# 05-Power_Sources.net
KiCad netlist of a schematic drawn in Altium Designer
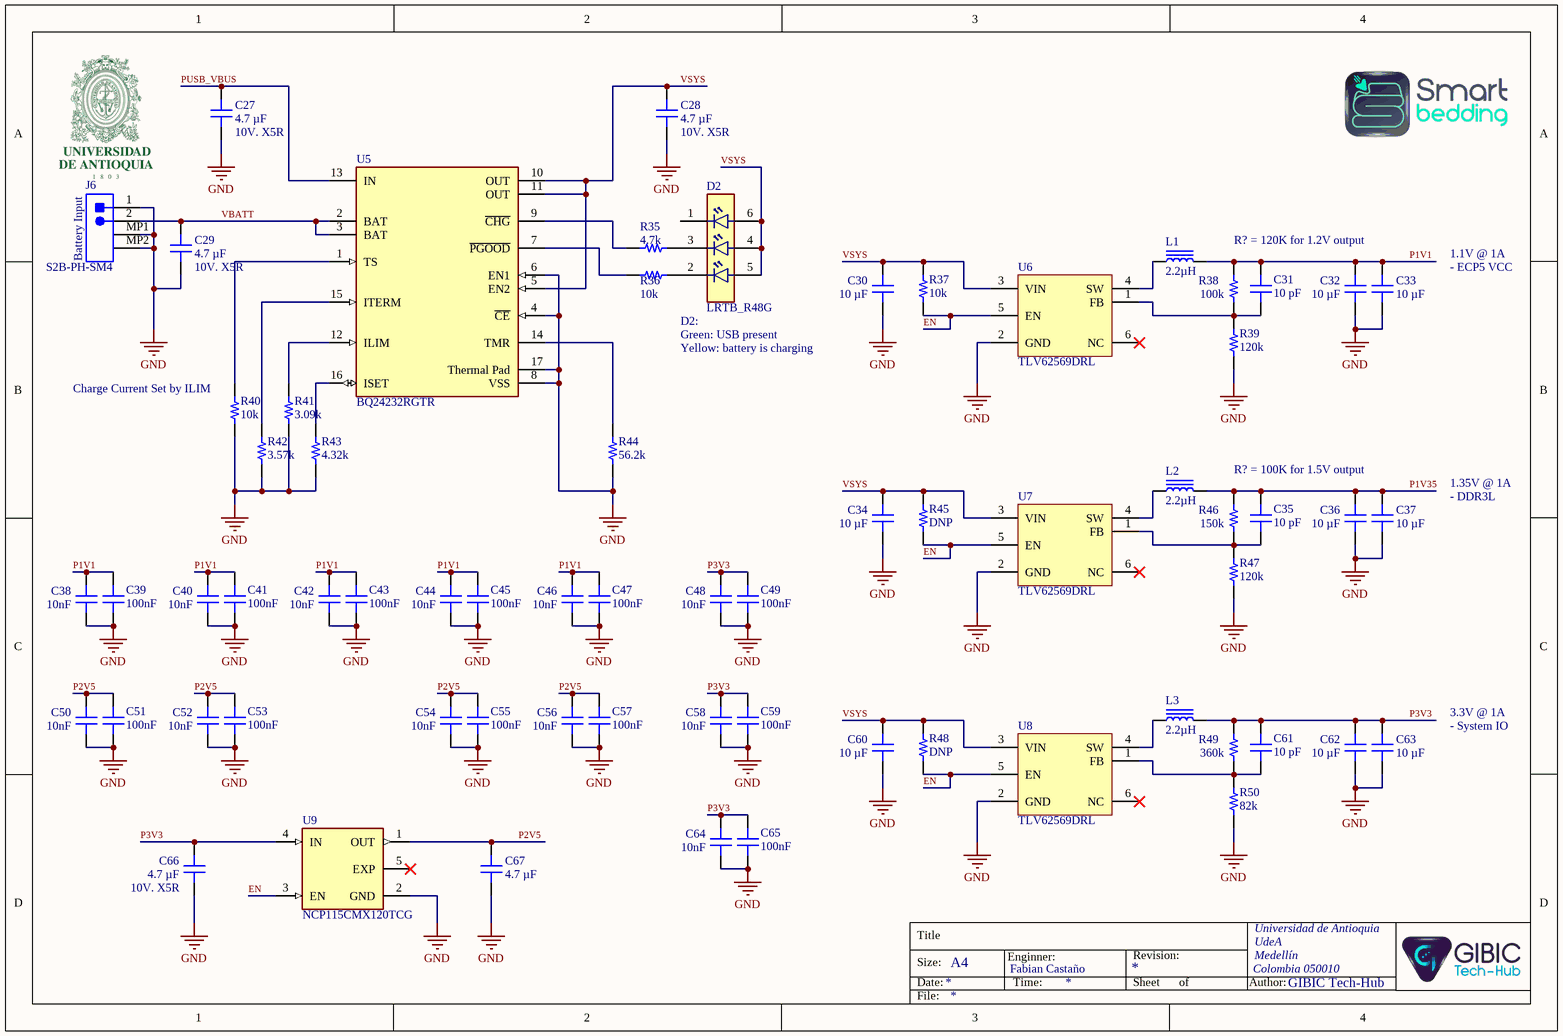
[diagram p0: 05-Power_Sources.SchDoc]

(export (version "E")
  (design (tool "Eeschema 10.0.6"))
  (components
    (comp (ref "C27")
      (value "4.7 µF")
      (footprint "CAP 0402_1005")
      (description "CAP CER 4.7UF 4V X6S 0402")
      (fields
        (field (name "PART NUMBER") "C1005X6S0G475M050BC")
        (field (name "MANUFACTURER") "TDK Corporation")
        (field (name "VOLTAGE") "10V. X5R")
        (field (name "LASTUPDATED") "3/01/2023 8:04:20 p. m.")
      )
      (libsource (lib "Celestial Altium Library - altium_library") (part "Capacitor"))
    )
    (comp (ref "C28")
      (value "4.7 µF")
      (footprint "CAP 0402_1005")
      (description "CAP CER 4.7UF 4V X6S 0402")
      (fields
        (field (name "PART NUMBER") "C1005X6S0G475M050BC")
        (field (name "MANUFACTURER") "TDK Corporation")
        (field (name "VOLTAGE") "10V. X5R")
        (field (name "LASTUPDATED") "3/01/2023 8:04:20 p. m.")
      )
      (libsource (lib "Celestial Altium Library - altium_library") (part "Capacitor"))
    )
    (comp (ref "C29")
      (value "4.7 µF")
      (footprint "CAP 0402_1005")
      (description "CAP CER 4.7UF 4V X6S 0402")
      (fields
        (field (name "PART NUMBER") "C1005X6S0G475M050BC")
        (field (name "MANUFACTURER") "TDK Corporation")
        (field (name "VOLTAGE") "10V. X5R")
        (field (name "LASTUPDATED") "3/01/2023 8:04:20 p. m.")
      )
      (libsource (lib "Celestial Altium Library - altium_library") (part "Capacitor"))
    )
    (comp (ref "C30")
      (value "10 µF")
      (footprint "CAP 0402_1005")
      (description "CAP CER 10UF 10V X5R 0402")
      (fields
        (field (name "PART NUMBER") "CL05A106MP8NUB8")
        (field (name "MANUFACTURER") "Samsung Electro-Mechanics")
        (field (name "LASTUPDATED") "3/01/2023 8:04:20 p. m.")
      )
      (libsource (lib "Celestial Altium Library - altium_library") (part "Capacitor"))
    )
    (comp (ref "C31")
      (value "10 pF")
      (footprint "CAP 0201_0603")
      (description "CAP CER 10PF 25V C0G/NP0 0201")
      (fields
        (field (name "PART NUMBER") "C0201C100J3GAC7867")
        (field (name "MANUFACTURER") "KEMET")
        (field (name "LASTUPDATED") "3/01/2023 8:01:19 p. m.")
      )
      (libsource (lib "Celestial Altium Library - altium_library") (part "Capacitor"))
    )
    (comp (ref "C32")
      (value "10 µF")
      (footprint "CAP 0402_1005")
      (description "CAP CER 10UF 10V X5R 0402")
      (fields
        (field (name "PART NUMBER") "CL05A106MP8NUB8")
        (field (name "MANUFACTURER") "Samsung Electro-Mechanics")
        (field (name "LASTUPDATED") "3/01/2023 8:04:20 p. m.")
      )
      (libsource (lib "Celestial Altium Library - altium_library") (part "Capacitor"))
    )
    (comp (ref "C33")
      (value "10 µF")
      (footprint "CAP 0402_1005")
      (description "CAP CER 10UF 10V X5R 0402")
      (fields
        (field (name "PART NUMBER") "CL05A106MP8NUB8")
        (field (name "MANUFACTURER") "Samsung Electro-Mechanics")
        (field (name "LASTUPDATED") "3/01/2023 8:04:20 p. m.")
      )
      (libsource (lib "Celestial Altium Library - altium_library") (part "Capacitor"))
    )
    (comp (ref "C34")
      (value "10 µF")
      (footprint "CAP 0402_1005")
      (description "CAP CER 10UF 10V X5R 0402")
      (fields
        (field (name "PART NUMBER") "CL05A106MP8NUB8")
        (field (name "MANUFACTURER") "Samsung Electro-Mechanics")
        (field (name "LASTUPDATED") "3/01/2023 8:04:20 p. m.")
      )
      (libsource (lib "Celestial Altium Library - altium_library") (part "Capacitor"))
    )
    (comp (ref "C35")
      (value "10 pF")
      (footprint "CAP 0201_0603")
      (description "CAP CER 10PF 25V C0G/NP0 0201")
      (fields
        (field (name "PART NUMBER") "C0201C100J3GAC7867")
        (field (name "MANUFACTURER") "KEMET")
        (field (name "LASTUPDATED") "3/01/2023 8:01:19 p. m.")
      )
      (libsource (lib "Celestial Altium Library - altium_library") (part "Capacitor"))
    )
    (comp (ref "C36")
      (value "10 µF")
      (footprint "CAP 0402_1005")
      (description "CAP CER 10UF 10V X5R 0402")
      (fields
        (field (name "PART NUMBER") "CL05A106MP8NUB8")
        (field (name "MANUFACTURER") "Samsung Electro-Mechanics")
        (field (name "LASTUPDATED") "3/01/2023 8:04:20 p. m.")
      )
      (libsource (lib "Celestial Altium Library - altium_library") (part "Capacitor"))
    )
    (comp (ref "C37")
      (value "10 µF")
      (footprint "CAP 0402_1005")
      (description "CAP CER 10UF 10V X5R 0402")
      (fields
        (field (name "PART NUMBER") "CL05A106MP8NUB8")
        (field (name "MANUFACTURER") "Samsung Electro-Mechanics")
        (field (name "LASTUPDATED") "3/01/2023 8:04:20 p. m.")
      )
      (libsource (lib "Celestial Altium Library - altium_library") (part "Capacitor"))
    )
    (comp (ref "C38")
      (value "10nF")
      (footprint "CAP 0201_0603")
      (description "CAP CER 10000PF 10V X7R 0201")
      (fields
        (field (name "PART NUMBER") "0201ZC103JAT2A")
        (field (name "MANUFACTURER") "AVX Corporation")
        (field (name "LASTUPDATED") "2/09/2020 12:59:12 a. m.")
      )
      (libsource (lib "Celestial Altium Library - altium_library") (part "Capacitor"))
    )
    (comp (ref "C39")
      (value "100nF")
      (footprint "CAP 0201_0603")
      (description "CAP CER 0.1UF 6.3V X6S 0201")
      (fields
        (field (name "PART NUMBER") "GRT033C80J104KE01J")
        (field (name "MANUFACTURER") "Murata Electronics")
        (field (name "LASTUPDATED") "3/01/2023 8:00:58 p. m.")
      )
      (libsource (lib "Celestial Altium Library - altium_library") (part "Capacitor"))
    )
    (comp (ref "C40")
      (value "10nF")
      (footprint "CAP 0201_0603")
      (description "CAP CER 10000PF 10V X7R 0201")
      (fields
        (field (name "PART NUMBER") "0201ZC103JAT2A")
        (field (name "MANUFACTURER") "AVX Corporation")
        (field (name "LASTUPDATED") "2/09/2020 12:59:12 a. m.")
      )
      (libsource (lib "Celestial Altium Library - altium_library") (part "Capacitor"))
    )
    (comp (ref "C41")
      (value "100nF")
      (footprint "CAP 0201_0603")
      (description "CAP CER 0.1UF 6.3V X6S 0201")
      (fields
        (field (name "PART NUMBER") "GRT033C80J104KE01J")
        (field (name "MANUFACTURER") "Murata Electronics")
        (field (name "LASTUPDATED") "3/01/2023 8:00:58 p. m.")
      )
      (libsource (lib "Celestial Altium Library - altium_library") (part "Capacitor"))
    )
    (comp (ref "C42")
      (value "10nF")
      (footprint "CAP 0201_0603")
      (description "CAP CER 10000PF 10V X7R 0201")
      (fields
        (field (name "PART NUMBER") "0201ZC103JAT2A")
        (field (name "MANUFACTURER") "AVX Corporation")
        (field (name "LASTUPDATED") "2/09/2020 12:59:12 a. m.")
      )
      (libsource (lib "Celestial Altium Library - altium_library") (part "Capacitor"))
    )
    (comp (ref "C43")
      (value "100nF")
      (footprint "CAP 0201_0603")
      (description "CAP CER 0.1UF 6.3V X6S 0201")
      (fields
        (field (name "PART NUMBER") "GRT033C80J104KE01J")
        (field (name "MANUFACTURER") "Murata Electronics")
        (field (name "LASTUPDATED") "3/01/2023 8:00:58 p. m.")
      )
      (libsource (lib "Celestial Altium Library - altium_library") (part "Capacitor"))
    )
    (comp (ref "C44")
      (value "10nF")
      (footprint "CAP 0201_0603")
      (description "CAP CER 10000PF 10V X7R 0201")
      (fields
        (field (name "PART NUMBER") "0201ZC103JAT2A")
        (field (name "MANUFACTURER") "AVX Corporation")
        (field (name "LASTUPDATED") "2/09/2020 12:59:12 a. m.")
      )
      (libsource (lib "Celestial Altium Library - altium_library") (part "Capacitor"))
    )
    (comp (ref "C45")
      (value "100nF")
      (footprint "CAP 0201_0603")
      (description "CAP CER 0.1UF 6.3V X6S 0201")
      (fields
        (field (name "PART NUMBER") "GRT033C80J104KE01J")
        (field (name "MANUFACTURER") "Murata Electronics")
        (field (name "LASTUPDATED") "3/01/2023 8:00:58 p. m.")
      )
      (libsource (lib "Celestial Altium Library - altium_library") (part "Capacitor"))
    )
    (comp (ref "C46")
      (value "10nF")
      (footprint "CAP 0201_0603")
      (description "CAP CER 10000PF 10V X7R 0201")
      (fields
        (field (name "PART NUMBER") "0201ZC103JAT2A")
        (field (name "MANUFACTURER") "AVX Corporation")
        (field (name "LASTUPDATED") "2/09/2020 12:59:12 a. m.")
      )
      (libsource (lib "Celestial Altium Library - altium_library") (part "Capacitor"))
    )
    (comp (ref "C47")
      (value "100nF")
      (footprint "CAP 0201_0603")
      (description "CAP CER 0.1UF 6.3V X6S 0201")
      (fields
        (field (name "PART NUMBER") "GRT033C80J104KE01J")
        (field (name "MANUFACTURER") "Murata Electronics")
        (field (name "LASTUPDATED") "3/01/2023 8:00:58 p. m.")
      )
      (libsource (lib "Celestial Altium Library - altium_library") (part "Capacitor"))
    )
    (comp (ref "C48")
      (value "10nF")
      (footprint "CAP 0201_0603")
      (description "CAP CER 10000PF 10V X7R 0201")
      (fields
        (field (name "PART NUMBER") "0201ZC103JAT2A")
        (field (name "MANUFACTURER") "AVX Corporation")
        (field (name "LASTUPDATED") "2/09/2020 12:59:12 a. m.")
      )
      (libsource (lib "Celestial Altium Library - altium_library") (part "Capacitor"))
    )
    (comp (ref "C49")
      (value "100nF")
      (footprint "CAP 0201_0603")
      (description "CAP CER 0.1UF 6.3V X6S 0201")
      (fields
        (field (name "PART NUMBER") "GRT033C80J104KE01J")
        (field (name "MANUFACTURER") "Murata Electronics")
        (field (name "LASTUPDATED") "3/01/2023 8:00:58 p. m.")
      )
      (libsource (lib "Celestial Altium Library - altium_library") (part "Capacitor"))
    )
    (comp (ref "C50")
      (value "10nF")
      (footprint "CAP 0201_0603")
      (description "CAP CER 10000PF 10V X7R 0201")
      (fields
        (field (name "PART NUMBER") "0201ZC103JAT2A")
        (field (name "MANUFACTURER") "AVX Corporation")
        (field (name "LASTUPDATED") "2/09/2020 12:59:12 a. m.")
      )
      (libsource (lib "Celestial Altium Library - altium_library") (part "Capacitor"))
    )
    (comp (ref "C51")
      (value "100nF")
      (footprint "CAP 0201_0603")
      (description "CAP CER 0.1UF 6.3V X6S 0201")
      (fields
        (field (name "PART NUMBER") "GRT033C80J104KE01J")
        (field (name "MANUFACTURER") "Murata Electronics")
        (field (name "LASTUPDATED") "3/01/2023 8:00:58 p. m.")
      )
      (libsource (lib "Celestial Altium Library - altium_library") (part "Capacitor"))
    )
    (comp (ref "C52")
      (value "10nF")
      (footprint "CAP 0201_0603")
      (description "CAP CER 10000PF 10V X7R 0201")
      (fields
        (field (name "PART NUMBER") "0201ZC103JAT2A")
        (field (name "MANUFACTURER") "AVX Corporation")
        (field (name "LASTUPDATED") "2/09/2020 12:59:12 a. m.")
      )
      (libsource (lib "Celestial Altium Library - altium_library") (part "Capacitor"))
    )
    (comp (ref "C53")
      (value "100nF")
      (footprint "CAP 0201_0603")
      (description "CAP CER 0.1UF 6.3V X6S 0201")
      (fields
        (field (name "PART NUMBER") "GRT033C80J104KE01J")
        (field (name "MANUFACTURER") "Murata Electronics")
        (field (name "LASTUPDATED") "3/01/2023 8:00:58 p. m.")
      )
      (libsource (lib "Celestial Altium Library - altium_library") (part "Capacitor"))
    )
    (comp (ref "C54")
      (value "10nF")
      (footprint "CAP 0201_0603")
      (description "CAP CER 10000PF 10V X7R 0201")
      (fields
        (field (name "PART NUMBER") "0201ZC103JAT2A")
        (field (name "MANUFACTURER") "AVX Corporation")
        (field (name "LASTUPDATED") "2/09/2020 12:59:12 a. m.")
      )
      (libsource (lib "Celestial Altium Library - altium_library") (part "Capacitor"))
    )
    (comp (ref "C55")
      (value "100nF")
      (footprint "CAP 0201_0603")
      (description "CAP CER 0.1UF 6.3V X6S 0201")
      (fields
        (field (name "PART NUMBER") "GRT033C80J104KE01J")
        (field (name "MANUFACTURER") "Murata Electronics")
        (field (name "LASTUPDATED") "3/01/2023 8:00:58 p. m.")
      )
      (libsource (lib "Celestial Altium Library - altium_library") (part "Capacitor"))
    )
    (comp (ref "C56")
      (value "10nF")
      (footprint "CAP 0201_0603")
      (description "CAP CER 10000PF 10V X7R 0201")
      (fields
        (field (name "PART NUMBER") "0201ZC103JAT2A")
        (field (name "MANUFACTURER") "AVX Corporation")
        (field (name "LASTUPDATED") "2/09/2020 12:59:12 a. m.")
      )
      (libsource (lib "Celestial Altium Library - altium_library") (part "Capacitor"))
    )
    (comp (ref "C57")
      (value "100nF")
      (footprint "CAP 0201_0603")
      (description "CAP CER 0.1UF 6.3V X6S 0201")
      (fields
        (field (name "PART NUMBER") "GRT033C80J104KE01J")
        (field (name "MANUFACTURER") "Murata Electronics")
        (field (name "LASTUPDATED") "3/01/2023 8:00:58 p. m.")
      )
      (libsource (lib "Celestial Altium Library - altium_library") (part "Capacitor"))
    )
    (comp (ref "C58")
      (value "10nF")
      (footprint "CAP 0201_0603")
      (description "CAP CER 10000PF 10V X7R 0201")
      (fields
        (field (name "PART NUMBER") "0201ZC103JAT2A")
        (field (name "MANUFACTURER") "AVX Corporation")
        (field (name "LASTUPDATED") "2/09/2020 12:59:12 a. m.")
      )
      (libsource (lib "Celestial Altium Library - altium_library") (part "Capacitor"))
    )
    (comp (ref "C59")
      (value "100nF")
      (footprint "CAP 0201_0603")
      (description "CAP CER 0.1UF 6.3V X6S 0201")
      (fields
        (field (name "PART NUMBER") "GRT033C80J104KE01J")
        (field (name "MANUFACTURER") "Murata Electronics")
        (field (name "LASTUPDATED") "3/01/2023 8:00:58 p. m.")
      )
      (libsource (lib "Celestial Altium Library - altium_library") (part "Capacitor"))
    )
    (comp (ref "C60")
      (value "10 µF")
      (footprint "CAP 0402_1005")
      (description "CAP CER 10UF 10V X5R 0402")
      (fields
        (field (name "PART NUMBER") "CL05A106MP8NUB8")
        (field (name "MANUFACTURER") "Samsung Electro-Mechanics")
        (field (name "LASTUPDATED") "3/01/2023 8:04:20 p. m.")
      )
      (libsource (lib "Celestial Altium Library - altium_library") (part "Capacitor"))
    )
    (comp (ref "C61")
      (value "10 pF")
      (footprint "CAP 0201_0603")
      (description "CAP CER 10PF 25V C0G/NP0 0201")
      (fields
        (field (name "PART NUMBER") "C0201C100J3GAC7867")
        (field (name "MANUFACTURER") "KEMET")
        (field (name "LASTUPDATED") "3/01/2023 8:01:19 p. m.")
      )
      (libsource (lib "Celestial Altium Library - altium_library") (part "Capacitor"))
    )
    (comp (ref "C62")
      (value "10 µF")
      (footprint "CAP 0402_1005")
      (description "CAP CER 10UF 10V X5R 0402")
      (fields
        (field (name "PART NUMBER") "CL05A106MP8NUB8")
        (field (name "MANUFACTURER") "Samsung Electro-Mechanics")
        (field (name "LASTUPDATED") "3/01/2023 8:04:20 p. m.")
      )
      (libsource (lib "Celestial Altium Library - altium_library") (part "Capacitor"))
    )
    (comp (ref "C63")
      (value "10 µF")
      (footprint "CAP 0402_1005")
      (description "CAP CER 10UF 10V X5R 0402")
      (fields
        (field (name "PART NUMBER") "CL05A106MP8NUB8")
        (field (name "MANUFACTURER") "Samsung Electro-Mechanics")
        (field (name "LASTUPDATED") "3/01/2023 8:04:20 p. m.")
      )
      (libsource (lib "Celestial Altium Library - altium_library") (part "Capacitor"))
    )
    (comp (ref "C64")
      (value "10nF")
      (footprint "CAP 0201_0603")
      (description "CAP CER 10000PF 10V X7R 0201")
      (fields
        (field (name "PART NUMBER") "0201ZC103JAT2A")
        (field (name "MANUFACTURER") "AVX Corporation")
        (field (name "LASTUPDATED") "2/09/2020 12:59:12 a. m.")
      )
      (libsource (lib "Celestial Altium Library - altium_library") (part "Capacitor"))
    )
    (comp (ref "C65")
      (value "100nF")
      (footprint "CAP 0201_0603")
      (description "CAP CER 0.1UF 6.3V X6S 0201")
      (fields
        (field (name "PART NUMBER") "GRT033C80J104KE01J")
        (field (name "MANUFACTURER") "Murata Electronics")
        (field (name "LASTUPDATED") "3/01/2023 8:00:58 p. m.")
      )
      (libsource (lib "Celestial Altium Library - altium_library") (part "Capacitor"))
    )
    (comp (ref "C66")
      (value "4.7 µF")
      (footprint "CAP 0402_1005")
      (description "CAP CER 4.7UF 4V X6S 0402")
      (fields
        (field (name "PART NUMBER") "C1005X6S0G475M050BC")
        (field (name "MANUFACTURER") "TDK Corporation")
        (field (name "VOLTAGE") "10V. X5R")
        (field (name "LASTUPDATED") "3/01/2023 8:04:20 p. m.")
      )
      (libsource (lib "Celestial Altium Library - altium_library") (part "Capacitor"))
    )
    (comp (ref "C67")
      (value "4.7 µF")
      (footprint "CAP 0402_1005")
      (description "CAP CER 4.7UF 4V X6S 0402")
      (fields
        (field (name "PART NUMBER") "C1005X6S0G475M050BC")
        (field (name "MANUFACTURER") "TDK Corporation")
        (field (name "LASTUPDATED") "3/01/2023 8:04:20 p. m.")
      )
      (libsource (lib "Celestial Altium Library - altium_library") (part "Capacitor"))
    )
    (comp (ref "D2")
      (value "LRTB_R48G")
      (footprint "LRTB_R48G")
      (description "RGB LED LRTB R48G")
      (libsource (lib "LRTB_R48G") (part "LRTB_R48G"))
    )
    (comp (ref "J6")
      (value "S2B-PH-SM4")
      (footprint "JST-S2B-PH-SM4-TB(LF)(SN)-2_V")
      (description "Male Header, Pitch 2 mm, 1 x 2 Position, Height 5.5 mm")
      (libsource (lib "S2B-PH-SM4") (part "S2B-PH-SM4"))
    )
    (comp (ref "L1")
      (value "2.2µH")
      (footprint "IND 0806_2016")
      (description "FIXED IND 2.2UH 1.4A 168MOHM")
      (fields
        (field (name "PART NUMBER") "ASMPM-0806-2R2M-T")
        (field (name "MANUFACTURER") "Abracon LLC")
        (field (name "LASTUPDATED") "2/01/2023 9:04:13 p. m.")
      )
      (libsource (lib "Celestial Altium Library - altium_library") (part "Inductor"))
    )
    (comp (ref "L2")
      (value "2.2µH")
      (footprint "IND 0806_2016")
      (description "FIXED IND 2.2UH 1.4A 168MOHM")
      (fields
        (field (name "PART NUMBER") "ASMPM-0806-2R2M-T")
        (field (name "MANUFACTURER") "Abracon LLC")
        (field (name "LASTUPDATED") "2/01/2023 9:04:13 p. m.")
      )
      (libsource (lib "Celestial Altium Library - altium_library") (part "Inductor"))
    )
    (comp (ref "L3")
      (value "2.2µH")
      (footprint "IND 0806_2016")
      (description "FIXED IND 2.2UH 1.4A 168MOHM")
      (fields
        (field (name "PART NUMBER") "ASMPM-0806-2R2M-T")
        (field (name "MANUFACTURER") "Abracon LLC")
        (field (name "LASTUPDATED") "2/01/2023 9:04:13 p. m.")
      )
      (libsource (lib "Celestial Altium Library - altium_library") (part "Inductor"))
    )
    (comp (ref "R35")
      (value "4.7k")
      (footprint "RES 0201_0603")
      (description "RES SMD 10K OHM 0.1% 1/20W 0201")
      (fields
        (field (name "PART NUMBER") "ERA-1AEB103C")
        (field (name "MANUFACTURER") "Panasonic Electronic Components")
        (field (name "LASTUPDATED") "3/01/2023 8:15:23 p. m.")
      )
      (libsource (lib "Celestial Altium Library - altium_library") (part "Resistor"))
    )
    (comp (ref "R36")
      (value "10k")
      (footprint "RES 0201_0603")
      (description "RES SMD 10K OHM 0.1% 1/20W 0201")
      (fields
        (field (name "PART NUMBER") "ERA-1AEB103C")
        (field (name "MANUFACTURER") "Panasonic Electronic Components")
        (field (name "LASTUPDATED") "3/01/2023 8:15:23 p. m.")
      )
      (libsource (lib "Celestial Altium Library - altium_library") (part "Resistor"))
    )
    (comp (ref "R37")
      (value "10k")
      (footprint "RES 0201_0603")
      (description "RES SMD 10K OHM 0.1% 1/20W 0201")
      (fields
        (field (name "PART NUMBER") "ERA-1AEB103C")
        (field (name "MANUFACTURER") "Panasonic Electronic Components")
        (field (name "LASTUPDATED") "3/01/2023 8:15:23 p. m.")
      )
      (libsource (lib "Celestial Altium Library - altium_library") (part "Resistor"))
    )
    (comp (ref "R38")
      (value "100k")
      (footprint "RES 0201_0603")
      (description "RES SMD 100K OHM 5% 1/20W 0201")
      (fields
        (field (name "PART NUMBER") "PFR03S-104-JNH")
        (field (name "MANUFACTURER") "Delta Electronics/Cyntec")
        (field (name "LASTUPDATED") "3/01/2023 8:15:21 p. m.")
      )
      (libsource (lib "Celestial Altium Library - altium_library") (part "Resistor"))
    )
    (comp (ref "R39")
      (value "120k")
      (footprint "RES 0201_0603")
      (description "RES SMD 100K OHM 5% 1/20W 0201")
      (fields
        (field (name "PART NUMBER") "PFR03S-104-JNH")
        (field (name "MANUFACTURER") "Delta Electronics/Cyntec")
        (field (name "LASTUPDATED") "3/01/2023 8:15:21 p. m.")
      )
      (libsource (lib "Celestial Altium Library - altium_library") (part "Resistor"))
    )
    (comp (ref "R40")
      (value "10k")
      (footprint "RES 0201_0603")
      (description "RES SMD 10K OHM 0.1% 1/20W 0201")
      (fields
        (field (name "PART NUMBER") "ERA-1AEB103C")
        (field (name "MANUFACTURER") "Panasonic Electronic Components")
        (field (name "LASTUPDATED") "3/01/2023 8:15:23 p. m.")
      )
      (libsource (lib "Celestial Altium Library - altium_library") (part "Resistor"))
    )
    (comp (ref "R41")
      (value "3.09k")
      (footprint "RES 0201_0603")
      (description "RES SMD 10K OHM 0.1% 1/20W 0201")
      (fields
        (field (name "PART NUMBER") "ERA-1AEB103C")
        (field (name "MANUFACTURER") "Panasonic Electronic Components")
        (field (name "LASTUPDATED") "3/01/2023 8:15:23 p. m.")
      )
      (libsource (lib "Celestial Altium Library - altium_library") (part "Resistor"))
    )
    (comp (ref "R42")
      (value "3.57k")
      (footprint "RES 0201_0603")
      (description "RES SMD 10K OHM 0.1% 1/20W 0201")
      (fields
        (field (name "PART NUMBER") "ERA-1AEB103C")
        (field (name "MANUFACTURER") "Panasonic Electronic Components")
        (field (name "LASTUPDATED") "3/01/2023 8:15:23 p. m.")
      )
      (libsource (lib "Celestial Altium Library - altium_library") (part "Resistor"))
    )
    (comp (ref "R43")
      (value "4.32k")
      (footprint "RES 0201_0603")
      (description "RES SMD 10K OHM 0.1% 1/20W 0201")
      (fields
        (field (name "PART NUMBER") "ERA-1AEB103C")
        (field (name "MANUFACTURER") "Panasonic Electronic Components")
        (field (name "LASTUPDATED") "3/01/2023 8:15:23 p. m.")
      )
      (libsource (lib "Celestial Altium Library - altium_library") (part "Resistor"))
    )
    (comp (ref "R44")
      (value "56.2k")
      (footprint "RES 0201_0603")
      (description "RES SMD 10K OHM 0.1% 1/20W 0201")
      (fields
        (field (name "PART NUMBER") "ERA-1AEB103C")
        (field (name "MANUFACTURER") "Panasonic Electronic Components")
        (field (name "LASTUPDATED") "3/01/2023 8:15:23 p. m.")
      )
      (libsource (lib "Celestial Altium Library - altium_library") (part "Resistor"))
    )
    (comp (ref "R45")
      (value "DNP")
      (footprint "RES 0201_0603")
      (description "RES SMD 10K OHM 0.1% 1/20W 0201")
      (fields
        (field (name "PART NUMBER") "ERA-1AEB103C")
        (field (name "MANUFACTURER") "Panasonic Electronic Components")
        (field (name "LASTUPDATED") "3/01/2023 8:15:23 p. m.")
      )
      (libsource (lib "Celestial Altium Library - altium_library") (part "Resistor"))
    )
    (comp (ref "R46")
      (value "150k")
      (footprint "RES 0201_0603")
      (description "RES SMD 100K OHM 5% 1/20W 0201")
      (fields
        (field (name "PART NUMBER") "PFR03S-104-JNH")
        (field (name "MANUFACTURER") "Delta Electronics/Cyntec")
        (field (name "LASTUPDATED") "3/01/2023 8:15:21 p. m.")
      )
      (libsource (lib "Celestial Altium Library - altium_library") (part "Resistor"))
    )
    (comp (ref "R47")
      (value "120k")
      (footprint "RES 0201_0603")
      (description "RES SMD 100K OHM 5% 1/20W 0201")
      (fields
        (field (name "PART NUMBER") "PFR03S-104-JNH")
        (field (name "MANUFACTURER") "Delta Electronics/Cyntec")
        (field (name "LASTUPDATED") "3/01/2023 8:15:21 p. m.")
      )
      (libsource (lib "Celestial Altium Library - altium_library") (part "Resistor"))
    )
    (comp (ref "R48")
      (value "DNP")
      (footprint "RES 0201_0603")
      (description "RES SMD 10K OHM 0.1% 1/20W 0201")
      (fields
        (field (name "PART NUMBER") "ERA-1AEB103C")
        (field (name "MANUFACTURER") "Panasonic Electronic Components")
        (field (name "LASTUPDATED") "3/01/2023 8:15:23 p. m.")
      )
      (libsource (lib "Celestial Altium Library - altium_library") (part "Resistor"))
    )
    (comp (ref "R49")
      (value "360k")
      (footprint "RES 0201_0603")
      (description "RES SMD 100K OHM 5% 1/20W 0201")
      (fields
        (field (name "PART NUMBER") "PFR03S-104-JNH")
        (field (name "MANUFACTURER") "Delta Electronics/Cyntec")
        (field (name "LASTUPDATED") "3/01/2023 8:15:21 p. m.")
      )
      (libsource (lib "Celestial Altium Library - altium_library") (part "Resistor"))
    )
    (comp (ref "R50")
      (value "82k")
      (footprint "RES 0201_0603")
      (description "RES SMD 100K OHM 5% 1/20W 0201")
      (fields
        (field (name "PART NUMBER") "PFR03S-104-JNH")
        (field (name "MANUFACTURER") "Delta Electronics/Cyntec")
        (field (name "LASTUPDATED") "3/01/2023 8:15:21 p. m.")
      )
      (libsource (lib "Celestial Altium Library - altium_library") (part "Resistor"))
    )
    (comp (ref "U5")
      (value "BQ24232RGTR")
      (footprint "FP-RGTR_MFG")
      (description "IC LI-ION CHARGE PWR MGMT 16QFN BQ24232RGTR")
      (libsource (lib "BQ24232RGTR") (part "BQ24232RGTR"))
    )
    (comp (ref "U6")
      (value "TLV62569DRL")
      (footprint "SOT50P160X60-6N")
      (description "2.5V-5.5V input, 2-A high efficiency step-down buck converter in SOT23 and SOT563 package")
      (libsource (lib "TLV62569DRL") (part "TLV62569DRL"))
    )
    (comp (ref "U7")
      (value "TLV62569DRL")
      (footprint "SOT50P160X60-6N")
      (description "2.5V-5.5V input, 2-A high efficiency step-down buck converter in SOT23 and SOT563 package")
      (libsource (lib "TLV62569DRL") (part "TLV62569DRL"))
    )
    (comp (ref "U8")
      (value "TLV62569DRL")
      (footprint "SOT50P160X60-6N")
      (description "2.5V-5.5V input, 2-A high efficiency step-down buck converter in SOT23 and SOT563 package")
      (libsource (lib "TLV62569DRL") (part "TLV62569DRL"))
    )
    (comp (ref "U9")
      (value "NCP115CMX120TCG")
      (footprint "VREG_NCP115CMX120TCG")
      (description "Linear Voltage Regulator IC Positive Fixed 1 Output 300mA 4-XDFN (1x1)")
      (fields (field (name "MF") "ON Semiconductor"))
      (libsource (lib "NCP115CMX120TCG") (part "NCP115CMX120TCG"))
    )
  )
  (nets
    (net (code "1") (name "/EN") (class "Default")
      (node (ref "R37") (pin "1") (pinfunction "1_1") (pintype "passive"))
      (node (ref "R45") (pin "1") (pinfunction "1_1") (pintype "passive"))
      (node (ref "R48") (pin "1") (pinfunction "1_1") (pintype "passive"))
      (node (ref "U6") (pin "5") (pinfunction "EN_5") (pintype "power_in"))
      (node (ref "U7") (pin "5") (pinfunction "EN_5") (pintype "power_in"))
      (node (ref "U8") (pin "5") (pinfunction "EN_5") (pintype "power_in"))
      (node (ref "U9") (pin "3") (pinfunction "EN_3") (pintype "input"))
    )
    (net (code "2") (name "/P1V1") (class "Default")
      (node (ref "C31") (pin "2") (pinfunction "2_2") (pintype "passive"))
      (node (ref "C32") (pin "2") (pinfunction "2_2") (pintype "passive"))
      (node (ref "C33") (pin "2") (pinfunction "2_2") (pintype "passive"))
      (node (ref "C38") (pin "2") (pinfunction "2_2") (pintype "passive"))
      (node (ref "C39") (pin "2") (pinfunction "2_2") (pintype "passive"))
      (node (ref "C40") (pin "2") (pinfunction "2_2") (pintype "passive"))
      (node (ref "C41") (pin "2") (pinfunction "2_2") (pintype "passive"))
      (node (ref "C42") (pin "2") (pinfunction "2_2") (pintype "passive"))
      (node (ref "C43") (pin "2") (pinfunction "2_2") (pintype "passive"))
      (node (ref "C44") (pin "2") (pinfunction "2_2") (pintype "passive"))
      (node (ref "C45") (pin "2") (pinfunction "2_2") (pintype "passive"))
      (node (ref "C46") (pin "2") (pinfunction "2_2") (pintype "passive"))
      (node (ref "C47") (pin "2") (pinfunction "2_2") (pintype "passive"))
      (node (ref "L1") (pin "2") (pinfunction "2_2") (pintype "passive"))
      (node (ref "R38") (pin "2") (pinfunction "2_2") (pintype "passive"))
    )
    (net (code "3") (name "/P1V35") (class "Default")
      (node (ref "C35") (pin "2") (pinfunction "2_2") (pintype "passive"))
      (node (ref "C36") (pin "2") (pinfunction "2_2") (pintype "passive"))
      (node (ref "C37") (pin "2") (pinfunction "2_2") (pintype "passive"))
      (node (ref "L2") (pin "2") (pinfunction "2_2") (pintype "passive"))
      (node (ref "R46") (pin "2") (pinfunction "2_2") (pintype "passive"))
    )
    (net (code "4") (name "/P2V5") (class "Default")
      (node (ref "C50") (pin "2") (pinfunction "2_2") (pintype "passive"))
      (node (ref "C51") (pin "2") (pinfunction "2_2") (pintype "passive"))
      (node (ref "C52") (pin "2") (pinfunction "2_2") (pintype "passive"))
      (node (ref "C53") (pin "2") (pinfunction "2_2") (pintype "passive"))
      (node (ref "C54") (pin "2") (pinfunction "2_2") (pintype "passive"))
      (node (ref "C55") (pin "2") (pinfunction "2_2") (pintype "passive"))
      (node (ref "C56") (pin "2") (pinfunction "2_2") (pintype "passive"))
      (node (ref "C57") (pin "2") (pinfunction "2_2") (pintype "passive"))
      (node (ref "C67") (pin "1") (pinfunction "1_1") (pintype "passive"))
      (node (ref "U9") (pin "1") (pinfunction "OUT_1") (pintype "output"))
    )
    (net (code "5") (name "/P3V3") (class "Default")
      (node (ref "C48") (pin "2") (pinfunction "2_2") (pintype "passive"))
      (node (ref "C49") (pin "2") (pinfunction "2_2") (pintype "passive"))
      (node (ref "C58") (pin "2") (pinfunction "2_2") (pintype "passive"))
      (node (ref "C59") (pin "2") (pinfunction "2_2") (pintype "passive"))
      (node (ref "C61") (pin "2") (pinfunction "2_2") (pintype "passive"))
      (node (ref "C62") (pin "2") (pinfunction "2_2") (pintype "passive"))
      (node (ref "C63") (pin "2") (pinfunction "2_2") (pintype "passive"))
      (node (ref "C64") (pin "2") (pinfunction "2_2") (pintype "passive"))
      (node (ref "C65") (pin "2") (pinfunction "2_2") (pintype "passive"))
      (node (ref "C66") (pin "1") (pinfunction "1_1") (pintype "passive"))
      (node (ref "L3") (pin "2") (pinfunction "2_2") (pintype "passive"))
      (node (ref "R49") (pin "2") (pinfunction "2_2") (pintype "passive"))
      (node (ref "U9") (pin "4") (pinfunction "IN_4") (pintype "input"))
    )
    (net (code "6") (name "/PUSB_VBUS") (class "Default")
      (node (ref "C27") (pin "1") (pinfunction "1_1") (pintype "passive"))
      (node (ref "U5") (pin "13") (pinfunction "IN_13") (pintype "power_in"))
    )
    (net (code "7") (name "/VBATT") (class "Default")
      (node (ref "C29") (pin "1") (pinfunction "1_1") (pintype "passive"))
      (node (ref "J6") (pin "2") (pinfunction "2_2") (pintype "passive"))
      (node (ref "U5") (pin "2") (pinfunction "BAT_2") (pintype "power_in"))
      (node (ref "U5") (pin "3") (pinfunction "BAT_3") (pintype "power_in"))
    )
    (net (code "8") (name "/VSYS") (class "Default")
      (node (ref "C28") (pin "1") (pinfunction "1_1") (pintype "passive"))
      (node (ref "C30") (pin "2") (pinfunction "2_2") (pintype "passive"))
      (node (ref "C34") (pin "2") (pinfunction "2_2") (pintype "passive"))
      (node (ref "C60") (pin "2") (pinfunction "2_2") (pintype "passive"))
      (node (ref "D2") (pin "4") (pinfunction "RED_A_4") (pintype "passive"))
      (node (ref "D2") (pin "5") (pinfunction "GREEN_A_5") (pintype "passive"))
      (node (ref "D2") (pin "6") (pinfunction "BLUE_A_6") (pintype "passive"))
      (node (ref "R37") (pin "2") (pinfunction "2_2") (pintype "passive"))
      (node (ref "R45") (pin "2") (pinfunction "2_2") (pintype "passive"))
      (node (ref "R48") (pin "2") (pinfunction "2_2") (pintype "passive"))
      (node (ref "U5") (pin "10") (pinfunction "OUT_10") (pintype "power_in"))
      (node (ref "U5") (pin "11") (pinfunction "OUT_11") (pintype "power_in"))
      (node (ref "U5") (pin "5") (pinfunction "EN2_5") (pintype "input"))
      (node (ref "U6") (pin "3") (pinfunction "VIN_3") (pintype "power_in"))
      (node (ref "U7") (pin "3") (pinfunction "VIN_3") (pintype "power_in"))
      (node (ref "U8") (pin "3") (pinfunction "VIN_3") (pintype "power_in"))
    )
    (net (code "9") (name "GND") (class "Default")
      (node (ref "C27") (pin "2") (pinfunction "2_2") (pintype "passive"))
      (node (ref "C28") (pin "2") (pinfunction "2_2") (pintype "passive"))
      (node (ref "C29") (pin "2") (pinfunction "2_2") (pintype "passive"))
      (node (ref "C30") (pin "1") (pinfunction "1_1") (pintype "passive"))
      (node (ref "C32") (pin "1") (pinfunction "1_1") (pintype "passive"))
      (node (ref "C33") (pin "1") (pinfunction "1_1") (pintype "passive"))
      (node (ref "C34") (pin "1") (pinfunction "1_1") (pintype "passive"))
      (node (ref "C36") (pin "1") (pinfunction "1_1") (pintype "passive"))
      (node (ref "C37") (pin "1") (pinfunction "1_1") (pintype "passive"))
      (node (ref "C38") (pin "1") (pinfunction "1_1") (pintype "passive"))
      (node (ref "C39") (pin "1") (pinfunction "1_1") (pintype "passive"))
      (node (ref "C40") (pin "1") (pinfunction "1_1") (pintype "passive"))
      (node (ref "C41") (pin "1") (pinfunction "1_1") (pintype "passive"))
      (node (ref "C42") (pin "1") (pinfunction "1_1") (pintype "passive"))
      (node (ref "C43") (pin "1") (pinfunction "1_1") (pintype "passive"))
      (node (ref "C44") (pin "1") (pinfunction "1_1") (pintype "passive"))
      (node (ref "C45") (pin "1") (pinfunction "1_1") (pintype "passive"))
      (node (ref "C46") (pin "1") (pinfunction "1_1") (pintype "passive"))
      (node (ref "C47") (pin "1") (pinfunction "1_1") (pintype "passive"))
      (node (ref "C48") (pin "1") (pinfunction "1_1") (pintype "passive"))
      (node (ref "C49") (pin "1") (pinfunction "1_1") (pintype "passive"))
      (node (ref "C50") (pin "1") (pinfunction "1_1") (pintype "passive"))
      (node (ref "C51") (pin "1") (pinfunction "1_1") (pintype "passive"))
      (node (ref "C52") (pin "1") (pinfunction "1_1") (pintype "passive"))
      (node (ref "C53") (pin "1") (pinfunction "1_1") (pintype "passive"))
      (node (ref "C54") (pin "1") (pinfunction "1_1") (pintype "passive"))
      (node (ref "C55") (pin "1") (pinfunction "1_1") (pintype "passive"))
      (node (ref "C56") (pin "1") (pinfunction "1_1") (pintype "passive"))
      (node (ref "C57") (pin "1") (pinfunction "1_1") (pintype "passive"))
      (node (ref "C58") (pin "1") (pinfunction "1_1") (pintype "passive"))
      (node (ref "C59") (pin "1") (pinfunction "1_1") (pintype "passive"))
      (node (ref "C60") (pin "1") (pinfunction "1_1") (pintype "passive"))
      (node (ref "C62") (pin "1") (pinfunction "1_1") (pintype "passive"))
      (node (ref "C63") (pin "1") (pinfunction "1_1") (pintype "passive"))
      (node (ref "C64") (pin "1") (pinfunction "1_1") (pintype "passive"))
      (node (ref "C65") (pin "1") (pinfunction "1_1") (pintype "passive"))
      (node (ref "C66") (pin "2") (pinfunction "2_2") (pintype "passive"))
      (node (ref "C67") (pin "2") (pinfunction "2_2") (pintype "passive"))
      (node (ref "J6") (pin "1") (pinfunction "1_1") (pintype "passive"))
      (node (ref "J6") (pin "MP1") (pinfunction "MP1_MP1") (pintype "passive"))
      (node (ref "J6") (pin "MP2") (pinfunction "MP2_MP2") (pintype "passive"))
      (node (ref "R39") (pin "1") (pinfunction "1_1") (pintype "passive"))
      (node (ref "R40") (pin "1") (pinfunction "1_1") (pintype "passive"))
      (node (ref "R41") (pin "1") (pinfunction "1_1") (pintype "passive"))
      (node (ref "R42") (pin "1") (pinfunction "1_1") (pintype "passive"))
      (node (ref "R43") (pin "1") (pinfunction "1_1") (pintype "passive"))
      (node (ref "R44") (pin "1") (pinfunction "1_1") (pintype "passive"))
      (node (ref "R47") (pin "1") (pinfunction "1_1") (pintype "passive"))
      (node (ref "R50") (pin "1") (pinfunction "1_1") (pintype "passive"))
      (node (ref "U5") (pin "17") (pinfunction "Thermal_Pad_17") (pintype "power_in"))
      (node (ref "U5") (pin "4") (pinfunction "~{CE}_4") (pintype "input"))
      (node (ref "U5") (pin "6") (pinfunction "EN1_6") (pintype "input"))
      (node (ref "U5") (pin "8") (pinfunction "VSS_8") (pintype "power_in"))
      (node (ref "U6") (pin "2") (pinfunction "GND_2") (pintype "power_in"))
      (node (ref "U7") (pin "2") (pinfunction "GND_2") (pintype "power_in"))
      (node (ref "U8") (pin "2") (pinfunction "GND_2") (pintype "power_in"))
      (node (ref "U9") (pin "2") (pinfunction "GND_2") (pintype "power_in"))
    )
    (net (code "10") (name "Net-(D2-GREEN_C)") (class "Default")
      (node (ref "D2") (pin "2") (pinfunction "GREEN_C_2") (pintype "passive"))
      (node (ref "R36") (pin "1") (pinfunction "1_1") (pintype "passive"))
    )
    (net (code "11") (name "Net-(D2-RED_C)") (class "Default")
      (node (ref "D2") (pin "3") (pinfunction "RED_C_3") (pintype "passive"))
      (node (ref "R35") (pin "1") (pinfunction "1_1") (pintype "passive"))
    )
    (net (code "12") (name "Net-(U5-ILIM)") (class "Default")
      (node (ref "R41") (pin "2") (pinfunction "2_2") (pintype "passive"))
      (node (ref "U5") (pin "12") (pinfunction "ILIM_12") (pintype "input"))
    )
    (net (code "13") (name "Net-(U5-ISET)") (class "Default")
      (node (ref "R43") (pin "2") (pinfunction "2_2") (pintype "passive"))
      (node (ref "U5") (pin "16") (pinfunction "ISET_16") (pintype "bidirectional"))
    )
    (net (code "14") (name "Net-(U5-ITERM)") (class "Default")
      (node (ref "R42") (pin "2") (pinfunction "2_2") (pintype "passive"))
      (node (ref "U5") (pin "15") (pinfunction "ITERM_15") (pintype "input"))
    )
    (net (code "15") (name "Net-(U5-TMR)") (class "Default")
      (node (ref "R44") (pin "2") (pinfunction "2_2") (pintype "passive"))
      (node (ref "U5") (pin "14") (pinfunction "TMR_14") (pintype "passive"))
    )
    (net (code "16") (name "Net-(U5-TS)") (class "Default")
      (node (ref "R40") (pin "2") (pinfunction "2_2") (pintype "passive"))
      (node (ref "U5") (pin "1") (pinfunction "TS_1") (pintype "input"))
    )
    (net (code "17") (name "Net-(U5-~{CHG})") (class "Default")
      (node (ref "R35") (pin "2") (pinfunction "2_2") (pintype "passive"))
      (node (ref "U5") (pin "9") (pinfunction "~{CHG}_9") (pintype "tri_state"))
    )
    (net (code "18") (name "Net-(U5-~{PGOOD})") (class "Default")
      (node (ref "R36") (pin "2") (pinfunction "2_2") (pintype "passive"))
      (node (ref "U5") (pin "7") (pinfunction "~{PGOOD}_7") (pintype "tri_state"))
    )
    (net (code "19") (name "Net-(U6-FB)") (class "Default")
      (node (ref "C31") (pin "1") (pinfunction "1_1") (pintype "passive"))
      (node (ref "R38") (pin "1") (pinfunction "1_1") (pintype "passive"))
      (node (ref "R39") (pin "2") (pinfunction "2_2") (pintype "passive"))
      (node (ref "U6") (pin "1") (pinfunction "FB_1") (pintype "passive"))
    )
    (net (code "20") (name "Net-(U6-SW)") (class "Default")
      (node (ref "L1") (pin "1") (pinfunction "1_1") (pintype "passive"))
      (node (ref "U6") (pin "4") (pinfunction "SW_4") (pintype "power_in"))
    )
    (net (code "21") (name "Net-(U7-FB)") (class "Default")
      (node (ref "C35") (pin "1") (pinfunction "1_1") (pintype "passive"))
      (node (ref "R46") (pin "1") (pinfunction "1_1") (pintype "passive"))
      (node (ref "R47") (pin "2") (pinfunction "2_2") (pintype "passive"))
      (node (ref "U7") (pin "1") (pinfunction "FB_1") (pintype "passive"))
    )
    (net (code "22") (name "Net-(U7-SW)") (class "Default")
      (node (ref "L2") (pin "1") (pinfunction "1_1") (pintype "passive"))
      (node (ref "U7") (pin "4") (pinfunction "SW_4") (pintype "power_in"))
    )
    (net (code "23") (name "Net-(U8-FB)") (class "Default")
      (node (ref "C61") (pin "1") (pinfunction "1_1") (pintype "passive"))
      (node (ref "R49") (pin "1") (pinfunction "1_1") (pintype "passive"))
      (node (ref "R50") (pin "2") (pinfunction "2_2") (pintype "passive"))
      (node (ref "U8") (pin "1") (pinfunction "FB_1") (pintype "passive"))
    )
    (net (code "24") (name "Net-(U8-SW)") (class "Default")
      (node (ref "L3") (pin "1") (pinfunction "1_1") (pintype "passive"))
      (node (ref "U8") (pin "4") (pinfunction "SW_4") (pintype "power_in"))
    )
    (net (code "25") (name "unconnected-(D2-BLUE_C-Pad1)") (class "Default")
      (node (ref "D2") (pin "1") (pinfunction "BLUE_C_1") (pintype "passive"))
    )
    (net (code "26") (name "unconnected-(U6-NC-Pad6)") (class "Default")
      (node (ref "U6") (pin "6") (pinfunction "NC_6") (pintype "power_in+no_connect"))
    )
    (net (code "27") (name "unconnected-(U7-NC-Pad6)") (class "Default")
      (node (ref "U7") (pin "6") (pinfunction "NC_6") (pintype "power_in+no_connect"))
    )
    (net (code "28") (name "unconnected-(U8-NC-Pad6)") (class "Default")
      (node (ref "U8") (pin "6") (pinfunction "NC_6") (pintype "power_in+no_connect"))
    )
    (net (code "29") (name "unconnected-(U9-EXP-Pad5)") (class "Default")
      (node (ref "U9") (pin "5") (pinfunction "EXP_5") (pintype "power_in+no_connect"))
    )
  )
)
